# Sheet1.net
KiCad netlist of a schematic drawn in Altium Designer
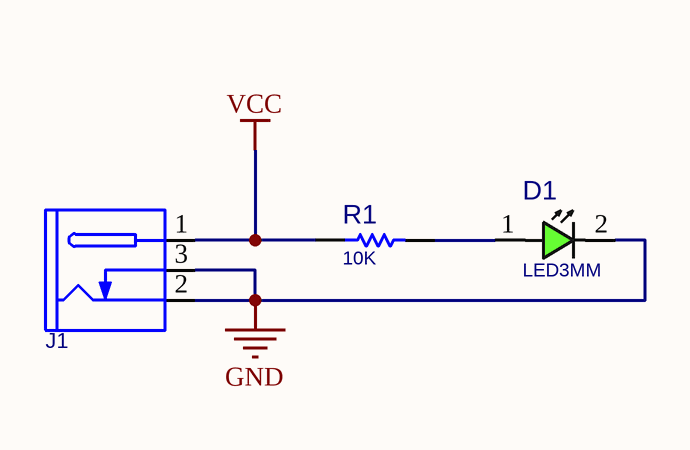
[diagram p0: Sheet1.SchDoc]

(export (version "E")
  (design (tool "Eeschema 10.0.6"))
  (components
    (comp (ref "D1")
      (value "LED3MM")
      (footprint "LED3MM")
      (description "LED, THD, 3MM, GREEN")
      (fields (field (name "MANF") "MANF") (field (name "MANF_P#") "MANF_PART#"))
      (libsource (lib "led(diode)") (part "LED_THD_3MM"))
    )
    (comp (ref "J1")
      (value "DC_POWER_JACK")
      (footprint "JAC_PWR1")
      (description "CONN, PWR JACK DC, PLUG DIAM 1.0MM RA THD")
      (fields (field (name "MANF") "CUI STACK") (field (name "MANF_P#") "PJ-031CH, PJ-031C"))
      (libsource (lib "conn_powerJack") (part "CONN_PWR_JACKR1"))
    )
    (comp (ref "R1")
      (value "10K")
      (footprint "R025W_AX04")
      (description "RESISTOR, THD")
      (fields (field (name "MANF_P#") "RK73H1ETTP4701F") (field (name "MANF") "KOA SPEER"))
      (libsource (lib "passive") (part "RES_THD"))
    )
  )
  (nets
    (net (code "1") (name "GND") (class "Default")
      (node (ref "D1") (pin "2") (pinfunction "CATHODE_2") (pintype "passive"))
      (node (ref "J1") (pin "2") (pinfunction "SLEEVE_2") (pintype "power_in"))
      (node (ref "J1") (pin "3") (pinfunction "INSERTION_DET_3") (pintype "power_in"))
    )
    (net (code "2") (name "Net-(D1-ANODE)") (class "Default")
      (node (ref "D1") (pin "1") (pinfunction "ANODE_1") (pintype "passive"))
      (node (ref "R1") (pin "2") (pinfunction "2_2") (pintype "passive"))
    )
    (net (code "3") (name "VCC") (class "Default")
      (node (ref "J1") (pin "1") (pinfunction "TIP_1") (pintype "power_in"))
      (node (ref "R1") (pin "1") (pinfunction "1_1") (pintype "passive"))
    )
  )
)
